# 4-20mA_Converter.net
KiCad netlist of a schematic drawn in Altium Designer
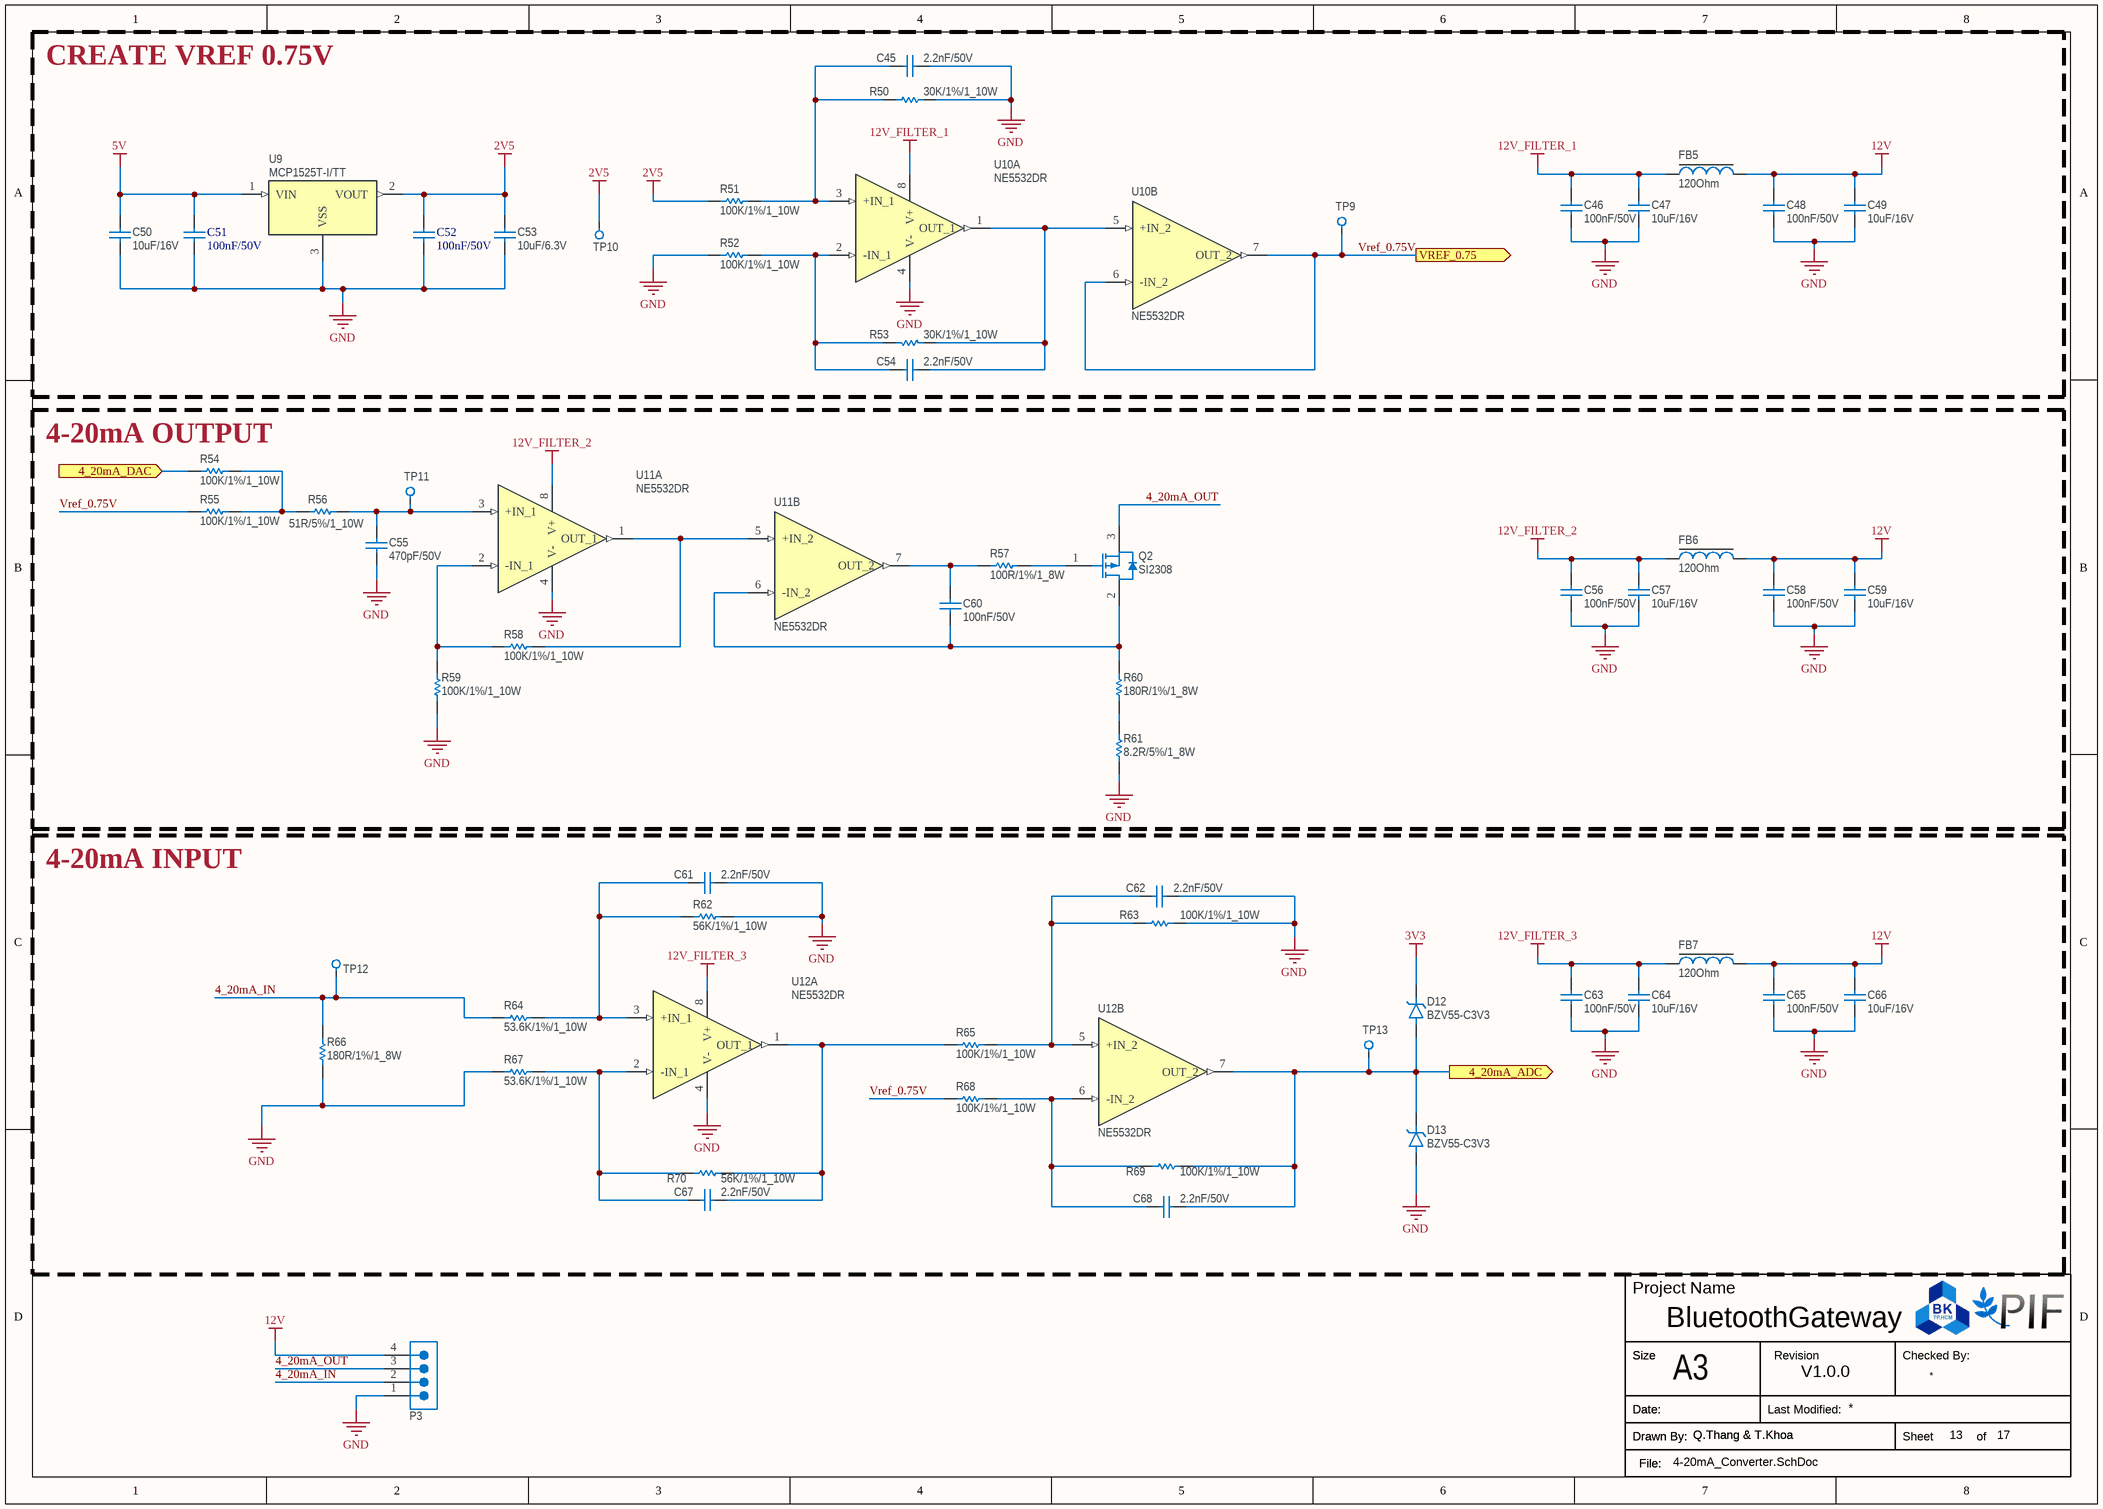
[diagram p0: 4-20mA_Converter.SchDoc]

(export (version "E")
  (design (tool "Eeschema 10.0.6"))
  (components
    (comp (ref "C45")
      (value "2.2nF/50V")
      (footprint "CAP_0603")
      (description "CAP, size 0603, 2.2nF, 50V")
      (fields (field (name "SUPPLY PART NUMBER") "CC0603KRX7R9BB222"))
      (libsource (lib "BluetoothTracking") (part "Ceramic_Cap_2.2nF_50V_0603"))
    )
    (comp (ref "C46")
      (value "100nF/50V")
      (footprint "CAP_0603")
      (description "CAP, size 0603, 100nF, 50V")
      (fields (field (name "SUPPLY PART NUMBER") "Tụ Gốm 0603 100nF (0.1uF) 50V"))
      (libsource (lib "BluetoothTracking") (part "Ceramic_Cap_100nF_50V_0603"))
    )
    (comp (ref "C47")
      (value "10uF/16V")
      (footprint "CAP_0603")
      (description "CAP, size 0603, 10uF, 16V")
      (fields (field (name "SUPPLY PART NUMBER") "Tụ Gốm 0603 10uF 16V"))
      (libsource (lib "BluetoothTracking") (part "Ceramic_Cap_10uF_16V_0603"))
    )
    (comp (ref "C48")
      (value "100nF/50V")
      (footprint "CAP_0603")
      (description "CAP, size 0603, 100nF, 50V")
      (fields (field (name "SUPPLY PART NUMBER") "Tụ Gốm 0603 100nF (0.1uF) 50V"))
      (libsource (lib "BluetoothTracking") (part "Ceramic_Cap_100nF_50V_0603"))
    )
    (comp (ref "C49")
      (value "10uF/16V")
      (footprint "CAP_0603")
      (description "CAP, size 0603, 10uF, 16V")
      (fields (field (name "SUPPLY PART NUMBER") "Tụ Gốm 0603 10uF 16V"))
      (libsource (lib "BluetoothTracking") (part "Ceramic_Cap_10uF_16V_0603"))
    )
    (comp (ref "C50")
      (value "10uF/16V")
      (footprint "CAP_0603")
      (description "CAP, size 0603, 10uF, 16V")
      (fields (field (name "SUPPLY PART NUMBER") "Tụ Gốm 0603 10uF 16V"))
      (libsource (lib "BluetoothTracking") (part "Ceramic_Cap_10uF_16V_0603"))
    )
    (comp (ref "C51")
      (value "100nF/50V")
      (footprint "CAP_0603")
      (description "CAP, size 0603, 100nF, 50V")
      (fields (field (name "SUPPLY PART NUMBER") "Tụ Gốm 0603 100nF (0.1uF) 50V"))
      (libsource (lib "BluetoothTracking") (part "Ceramic_Cap_100nF_50V_0603"))
    )
    (comp (ref "C52")
      (value "100nF/50V")
      (footprint "CAP_0603")
      (description "CAP, size 0603, 100nF, 50V")
      (fields (field (name "SUPPLY PART NUMBER") "Tụ Gốm 0603 100nF (0.1uF) 50V"))
      (libsource (lib "BluetoothTracking") (part "Ceramic_Cap_100nF_50V_0603"))
    )
    (comp (ref "C53")
      (value "10uF/6.3V")
      (footprint "CAP_0603")
      (description "CAP, size 0603, 10uF, 6.3V")
      (fields (field (name "SUPPLY PART NUMBER") "CC0603KRX5R5BB106"))
      (libsource (lib "BluetoothTracking") (part "Ceramic_Cap_10uF_6.3V_0603"))
    )
    (comp (ref "C54")
      (value "2.2nF/50V")
      (footprint "CAP_0603")
      (description "CAP, size 0603, 2.2nF, 50V")
      (fields (field (name "SUPPLY PART NUMBER") "CC0603KRX7R9BB222"))
      (libsource (lib "BluetoothTracking") (part "Ceramic_Cap_2.2nF_50V_0603"))
    )
    (comp (ref "C55")
      (value "470pF/50V")
      (footprint "CAP_0603")
      (description "CAP, size 0603, 470pF, 50V")
      (fields (field (name "SUPPLY PART NUMBER") "Tụ Gốm 0603 470pF 50V"))
      (libsource (lib "BluetoothTracking") (part "Ceramic_Cap_470pF_50V_0603"))
    )
    (comp (ref "C56")
      (value "100nF/50V")
      (footprint "CAP_0603")
      (description "CAP, size 0603, 100nF, 50V")
      (fields (field (name "SUPPLY PART NUMBER") "Tụ Gốm 0603 100nF (0.1uF) 50V"))
      (libsource (lib "BluetoothTracking") (part "Ceramic_Cap_100nF_50V_0603"))
    )
    (comp (ref "C57")
      (value "10uF/16V")
      (footprint "CAP_0603")
      (description "CAP, size 0603, 10uF, 16V")
      (fields (field (name "SUPPLY PART NUMBER") "Tụ Gốm 0603 10uF 16V"))
      (libsource (lib "BluetoothTracking") (part "Ceramic_Cap_10uF_16V_0603"))
    )
    (comp (ref "C58")
      (value "100nF/50V")
      (footprint "CAP_0603")
      (description "CAP, size 0603, 100nF, 50V")
      (fields (field (name "SUPPLY PART NUMBER") "Tụ Gốm 0603 100nF (0.1uF) 50V"))
      (libsource (lib "BluetoothTracking") (part "Ceramic_Cap_100nF_50V_0603"))
    )
    (comp (ref "C59")
      (value "10uF/16V")
      (footprint "CAP_0603")
      (description "CAP, size 0603, 10uF, 16V")
      (fields (field (name "SUPPLY PART NUMBER") "Tụ Gốm 0603 10uF 16V"))
      (libsource (lib "BluetoothTracking") (part "Ceramic_Cap_10uF_16V_0603"))
    )
    (comp (ref "C60")
      (value "100nF/50V")
      (footprint "CAP_0603")
      (description "CAP, size 0603, 100nF, 50V")
      (fields (field (name "SUPPLY PART NUMBER") "Tụ Gốm 0603 100nF (0.1uF) 50V"))
      (libsource (lib "BluetoothTracking") (part "Ceramic_Cap_100nF_50V_0603"))
    )
    (comp (ref "C61")
      (value "2.2nF/50V")
      (footprint "CAP_0603")
      (description "CAP, size 0603, 2.2nF, 50V")
      (fields (field (name "SUPPLY PART NUMBER") "CC0603KRX7R9BB222"))
      (libsource (lib "BluetoothTracking") (part "Ceramic_Cap_2.2nF_50V_0603"))
    )
    (comp (ref "C62")
      (value "2.2nF/50V")
      (footprint "CAP_0603")
      (description "CAP, size 0603, 2.2nF, 50V")
      (fields (field (name "SUPPLY PART NUMBER") "CC0603KRX7R9BB222"))
      (libsource (lib "BluetoothTracking") (part "Ceramic_Cap_2.2nF_50V_0603"))
    )
    (comp (ref "C63")
      (value "100nF/50V")
      (footprint "CAP_0603")
      (description "CAP, size 0603, 100nF, 50V")
      (fields (field (name "SUPPLY PART NUMBER") "Tụ Gốm 0603 100nF (0.1uF) 50V"))
      (libsource (lib "BluetoothTracking") (part "Ceramic_Cap_100nF_50V_0603"))
    )
    (comp (ref "C64")
      (value "10uF/16V")
      (footprint "CAP_0603")
      (description "CAP, size 0603, 10uF, 16V")
      (fields (field (name "SUPPLY PART NUMBER") "Tụ Gốm 0603 10uF 16V"))
      (libsource (lib "BluetoothTracking") (part "Ceramic_Cap_10uF_16V_0603"))
    )
    (comp (ref "C65")
      (value "100nF/50V")
      (footprint "CAP_0603")
      (description "CAP, size 0603, 100nF, 50V")
      (fields (field (name "SUPPLY PART NUMBER") "Tụ Gốm 0603 100nF (0.1uF) 50V"))
      (libsource (lib "BluetoothTracking") (part "Ceramic_Cap_100nF_50V_0603"))
    )
    (comp (ref "C66")
      (value "10uF/16V")
      (footprint "CAP_0603")
      (description "CAP, size 0603, 10uF, 16V")
      (fields (field (name "SUPPLY PART NUMBER") "Tụ Gốm 0603 10uF 16V"))
      (libsource (lib "BluetoothTracking") (part "Ceramic_Cap_10uF_16V_0603"))
    )
    (comp (ref "C67")
      (value "2.2nF/50V")
      (footprint "CAP_0603")
      (description "CAP, size 0603, 2.2nF, 50V")
      (fields (field (name "SUPPLY PART NUMBER") "CC0603KRX7R9BB222"))
      (libsource (lib "BluetoothTracking") (part "Ceramic_Cap_2.2nF_50V_0603"))
    )
    (comp (ref "C68")
      (value "2.2nF/50V")
      (footprint "CAP_0603")
      (description "CAP, size 0603, 2.2nF, 50V")
      (fields (field (name "SUPPLY PART NUMBER") "CC0603KRX7R9BB222"))
      (libsource (lib "BluetoothTracking") (part "Ceramic_Cap_2.2nF_50V_0603"))
    )
    (comp (ref "D12")
      (value "BZV55-C3V3")
      (footprint "SOD-80")
      (description "DIODE ZENER 3.3V 500 mW")
      (libsource (lib "BluetoothTracking") (part "Diode_BZV55C3V3"))
    )
    (comp (ref "D13")
      (value "BZV55-C3V3")
      (footprint "SOD-80")
      (description "DIODE ZENER 3.3V 500 mW")
      (libsource (lib "BluetoothTracking") (part "Diode_BZV55C3V3"))
    )
    (comp (ref "FB5")
      (value "120Ohm")
      (footprint "Ferrite_Bead_0805")
      (description "Ferrite Bead, size 0805, 120Ohm, 2A")
      (fields (field (name "SUPPLY PART NUMBER") "CBW201209U121T Ferrite Beads 2A 120 Ohm 0805"))
      (libsource (lib "BluetoothTracking") (part "Ferrite_Bead_120Ohm_2A_0805"))
    )
    (comp (ref "FB6")
      (value "120Ohm")
      (footprint "Ferrite_Bead_0805")
      (description "Ferrite Bead, size 0805, 120Ohm, 2A")
      (fields (field (name "SUPPLY PART NUMBER") "CBW201209U121T Ferrite Beads 2A 120 Ohm 0805"))
      (libsource (lib "BluetoothTracking") (part "Ferrite_Bead_120Ohm_2A_0805"))
    )
    (comp (ref "FB7")
      (value "120Ohm")
      (footprint "Ferrite_Bead_0805")
      (description "Ferrite Bead, size 0805, 120Ohm, 2A")
      (fields (field (name "SUPPLY PART NUMBER") "CBW201209U121T Ferrite Beads 2A 120 Ohm 0805"))
      (libsource (lib "BluetoothTracking") (part "Ferrite_Bead_120Ohm_2A_0805"))
    )
    (comp (ref "P3")
      (value "3.81mm_4P")
      (footprint "Terminal_Block_3.81mm_4P")
      (description "Terminal Block THT, pitch 3.81mm, 4p, 300V 10A")
      (fields
        (field (name "SUPPLY PART NUMBER") "UL-3.81-4-R Terminal Block Plug-in Hàn PCB 4 Chân Cong 3.81mm 300V 10A ULO")
      )
      (libsource (lib "BluetoothTracking") (part "Terminal_Block_3.81mm_4P"))
    )
    (comp (ref "Q2")
      (value "SI2308")
      (footprint "SOT-23")
      (description "SI2308 SOT23 MOSFET N-CH 2A 60V")
      (libsource (lib "BluetoothTracking") (part "SI2308"))
    )
    (comp (ref "R50")
      (value "30K/1%/1_10W")
      (footprint "Resistor_0603")
      (description "Resistor 0603 30KOhm 1% 1_10W")
      (fields (field (name "SUPPLY PART NUMBER") "Điện Trở 30 KOhm 0603 1%"))
      (libsource (lib "BluetoothTracking") (part "Res_30K_0603_1%"))
    )
    (comp (ref "R51")
      (value "100K/1%/1_10W")
      (footprint "Resistor_0603")
      (description "Resistor 0603 100KOhm 1% 1_10W")
      (fields (field (name "SUPPLY PART NUMBER") "Điện Trở 100 KOhm 0603 1%"))
      (libsource (lib "BluetoothTracking") (part "Res_100K_0603_1%"))
    )
    (comp (ref "R52")
      (value "100K/1%/1_10W")
      (footprint "Resistor_0603")
      (description "Resistor 0603 100KOhm 1% 1_10W")
      (fields (field (name "SUPPLY PART NUMBER") "Điện Trở 100 KOhm 0603 1%"))
      (libsource (lib "BluetoothTracking") (part "Res_100K_0603_1%"))
    )
    (comp (ref "R53")
      (value "30K/1%/1_10W")
      (footprint "Resistor_0603")
      (description "Resistor 0603 30KOhm 1% 1_10W")
      (fields (field (name "SUPPLY PART NUMBER") "Điện Trở 30 KOhm 0603 1%"))
      (libsource (lib "BluetoothTracking") (part "Res_30K_0603_1%"))
    )
    (comp (ref "R54")
      (value "100K/1%/1_10W")
      (footprint "Resistor_0603")
      (description "Resistor 0603 100KOhm 1% 1_10W")
      (fields (field (name "SUPPLY PART NUMBER") "Điện Trở 100 KOhm 0603 1%"))
      (libsource (lib "BluetoothTracking") (part "Res_100K_0603_1%"))
    )
    (comp (ref "R55")
      (value "100K/1%/1_10W")
      (footprint "Resistor_0603")
      (description "Resistor 0603 100KOhm 1% 1_10W")
      (fields (field (name "SUPPLY PART NUMBER") "Điện Trở 100 KOhm 0603 1%"))
      (libsource (lib "BluetoothTracking") (part "Res_100K_0603_1%"))
    )
    (comp (ref "R56")
      (value "51R/5%/1_10W")
      (footprint "Resistor_0603")
      (description "Resistor 0603 51 Ohm 5% 1_10W")
      (fields (field (name "SUPPLY PART NUMBER") "Điện Trở 51 Ohm 0603 5%"))
      (libsource (lib "BluetoothTracking") (part "Res_51R_0603_5%"))
    )
    (comp (ref "R57")
      (value "100R/1%/1_8W")
      (footprint "Resistor_0603")
      (description "Resistor 0805 100 Ohm 1% 1_8W")
      (fields (field (name "SUPPLY PART NUMBER") "Điện Trở 100 Ohm 0805 1%"))
      (libsource (lib "BluetoothTracking") (part "Res_100R_0805_1%"))
    )
    (comp (ref "R58")
      (value "100K/1%/1_10W")
      (footprint "Resistor_0603")
      (description "Resistor 0603 100KOhm 1% 1_10W")
      (fields (field (name "SUPPLY PART NUMBER") "Điện Trở 100 KOhm 0603 1%"))
      (libsource (lib "BluetoothTracking") (part "Res_100K_0603_1%"))
    )
    (comp (ref "R59")
      (value "100K/1%/1_10W")
      (footprint "Resistor_0603")
      (description "Resistor 0603 100KOhm 1% 1_10W")
      (fields (field (name "SUPPLY PART NUMBER") "Điện Trở 100 KOhm 0603 1%"))
      (libsource (lib "BluetoothTracking") (part "Res_100K_0603_1%"))
    )
    (comp (ref "R60")
      (value "180R/1%/1_8W")
      (footprint "Resistor_0805")
      (description "Resistor 0805 180 Ohm 1% 1_8W")
      (fields (field (name "SUPPLY PART NUMBER") "Điện Trở 180 Ohm 0805 1%"))
      (libsource (lib "BluetoothTracking") (part "Res_180R_0805_1%"))
    )
    (comp (ref "R61")
      (value "8.2R/5%/1_8W")
      (footprint "Resistor_0805")
      (description "Resistor 0805 8.2 Ohm 5% 1_8W")
      (fields (field (name "SUPPLY PART NUMBER") "Điện Trở 8.2 Ohm 0805 5%"))
      (libsource (lib "BluetoothTracking") (part "Res_8.2R_0805_5%"))
    )
    (comp (ref "R62")
      (value "56K/1%/1_10W")
      (footprint "Resistor_0603")
      (description "Resistor 0603 56KOhm 1% 1_10W")
      (fields (field (name "SUPPLY PART NUMBER") "Điện Trở 56 KOhm 0603 1%"))
      (libsource (lib "BluetoothTracking") (part "Res_56K_0603_1%"))
    )
    (comp (ref "R63")
      (value "100K/1%/1_10W")
      (footprint "Resistor_0603")
      (description "Resistor 0603 100KOhm 1% 1_10W")
      (fields (field (name "SUPPLY PART NUMBER") "Điện Trở 100 KOhm 0603 1%"))
      (libsource (lib "BluetoothTracking") (part "Res_100K_0603_1%"))
    )
    (comp (ref "R64")
      (value "53.6K/1%/1_10W")
      (footprint "Resistor_0603")
      (description "Resistor 0603 53.6KOhm 1% 1_10W")
      (fields (field (name "SUPPLY PART NUMBER") "Điện Trở 53.6 KOhm 0603 1%"))
      (libsource (lib "BluetoothTracking") (part "Res_53.6K_0603_1%"))
    )
    (comp (ref "R65")
      (value "100K/1%/1_10W")
      (footprint "Resistor_0603")
      (description "Resistor 0603 100KOhm 1% 1_10W")
      (fields (field (name "SUPPLY PART NUMBER") "Điện Trở 100 KOhm 0603 1%"))
      (libsource (lib "BluetoothTracking") (part "Res_100K_0603_1%"))
    )
    (comp (ref "R66")
      (value "180R/1%/1_8W")
      (footprint "Resistor_0805")
      (description "Resistor 0805 180 Ohm 1% 1_8W")
      (fields (field (name "SUPPLY PART NUMBER") "Điện Trở 180 Ohm 0805 1%"))
      (libsource (lib "BluetoothTracking") (part "Res_180R_0805_1%"))
    )
    (comp (ref "R67")
      (value "53.6K/1%/1_10W")
      (footprint "Resistor_0603")
      (description "Resistor 0603 53.6KOhm 1% 1_10W")
      (fields (field (name "SUPPLY PART NUMBER") "Điện Trở 53.6 KOhm 0603 1%"))
      (libsource (lib "BluetoothTracking") (part "Res_53.6K_0603_1%"))
    )
    (comp (ref "R68")
      (value "100K/1%/1_10W")
      (footprint "Resistor_0603")
      (description "Resistor 0603 100KOhm 1% 1_10W")
      (fields (field (name "SUPPLY PART NUMBER") "Điện Trở 100 KOhm 0603 1%"))
      (libsource (lib "BluetoothTracking") (part "Res_100K_0603_1%"))
    )
    (comp (ref "R69")
      (value "100K/1%/1_10W")
      (footprint "Resistor_0603")
      (description "Resistor 0603 100KOhm 1% 1_10W")
      (fields (field (name "SUPPLY PART NUMBER") "Điện Trở 100 KOhm 0603 1%"))
      (libsource (lib "BluetoothTracking") (part "Res_100K_0603_1%"))
    )
    (comp (ref "R70")
      (value "56K/1%/1_10W")
      (footprint "Resistor_0603")
      (description "Resistor 0603 56KOhm 1% 1_10W")
      (fields (field (name "SUPPLY PART NUMBER") "Điện Trở 56 KOhm 0603 1%"))
      (libsource (lib "BluetoothTracking") (part "Res_56K_0603_1%"))
    )
    (comp (ref "TP9")
      (value "VREF_0.75V")
      (footprint "TestPoint_Pad_3.0x3.0mm")
      (libsource (lib "BluetoothTracking") (part "Testpoint_SMD"))
    )
    (comp (ref "TP10")
      (value "2V5")
      (footprint "TestPoint_Pad_3.0x3.0mm")
      (libsource (lib "BluetoothTracking") (part "Testpoint_SMD"))
    )
    (comp (ref "TP11")
      (value "4-20mA_DAC")
      (footprint "TestPoint_THTPad_D1.5mm_Drill0.7mm")
      (description "Test Point TEST-1BK")
      (libsource (lib "BluetoothTracking") (part "Testpoint_TH"))
    )
    (comp (ref "TP12")
      (value "4_20mA_IN")
      (footprint "TestPoint_THTPad_D1.5mm_Drill0.7mm")
      (description "Test Point TEST-1BK")
      (libsource (lib "BluetoothTracking") (part "Testpoint_TH"))
    )
    (comp (ref "TP13")
      (value "4-20mA_ADC")
      (footprint "TestPoint_THTPad_D1.5mm_Drill0.7mm")
      (description "Test Point TEST-1BK")
      (libsource (lib "BluetoothTracking") (part "Testpoint_TH"))
    )
    (comp (ref "U9")
      (value "MCP1525T-I/TT")
      (footprint "SOT-23")
      (description "Voltage Reference IC 2.5V")
      (fields (field (name "SUPPLY PART NUMBER") "MCP1525T-I/TT IC Tham Chiếu Điện Áp 2.5V SOT-23"))
      (libsource (lib "BluetoothTracking") (part "MCP1525T-I/TT"))
    )
    (comp (ref "U10")
      (value "NE5532DR")
      (footprint "SOIC-8")
      (description "Low Noise Single/Dual Operational Amplifier - SOIC-8")
      (libsource (lib "BluetoothTracking") (part "NE5532DR"))
    )
    (comp (ref "U11")
      (value "NE5532DR")
      (footprint "SOIC-8")
      (description "Low Noise Single/Dual Operational Amplifier - SOIC-8")
      (libsource (lib "BluetoothTracking") (part "NE5532DR"))
    )
    (comp (ref "U12")
      (value "NE5532DR")
      (footprint "SOIC-8")
      (description "Low Noise Single/Dual Operational Amplifier - SOIC-8")
      (libsource (lib "BluetoothTracking") (part "NE5532DR"))
    )
  )
  (nets
    (net (code "1") (name "/4_20mA_ADC") (class "Default")
      (node (ref "C68") (pin "2") (pinfunction "2_2") (pintype "passive"))
      (node (ref "D12") (pin "A") (pinfunction "A_A") (pintype "passive"))
      (node (ref "D13") (pin "C") (pinfunction "C_C") (pintype "passive"))
      (node (ref "R69") (pin "2") (pinfunction "2_2") (pintype "passive"))
      (node (ref "TP13") (pin "1") (pinfunction "1_1") (pintype "passive"))
      (node (ref "U12") (pin "7") (pinfunction "OUT_2_7") (pintype "output"))
    )
    (net (code "2") (name "/4_20mA_DAC") (class "Default")
      (node (ref "R54") (pin "1") (pinfunction "1_1") (pintype "passive"))
    )
    (net (code "3") (name "/4_20mA_IN") (class "Default")
      (node (ref "P3") (pin "2") (pinfunction "2_2") (pintype "passive"))
      (node (ref "R64") (pin "1") (pinfunction "1_1") (pintype "passive"))
      (node (ref "R66") (pin "2") (pinfunction "2_2") (pintype "passive"))
      (node (ref "TP12") (pin "1") (pinfunction "1_1") (pintype "passive"))
    )
    (net (code "4") (name "/4_20mA_OUT") (class "Default")
      (node (ref "P3") (pin "3") (pinfunction "3_3") (pintype "passive"))
      (node (ref "Q2") (pin "3") (pinfunction "DRAIN_3") (pintype "passive"))
    )
    (net (code "5") (name "/Vref_0.75V") (class "Default")
      (node (ref "R55") (pin "1") (pinfunction "1_1") (pintype "passive"))
      (node (ref "R68") (pin "1") (pinfunction "1_1") (pintype "passive"))
      (node (ref "TP9") (pin "1") (pinfunction "1_1") (pintype "passive"))
      (node (ref "U10") (pin "6") (pinfunction "-IN_2_6") (pintype "input"))
      (node (ref "U10") (pin "7") (pinfunction "OUT_2_7") (pintype "output"))
    )
    (net (code "6") (name "2V5") (class "Default")
      (node (ref "C52") (pin "2") (pinfunction "2_2") (pintype "passive"))
      (node (ref "C53") (pin "2") (pinfunction "2_2") (pintype "passive"))
      (node (ref "R51") (pin "1") (pinfunction "1_1") (pintype "passive"))
      (node (ref "TP10") (pin "1") (pinfunction "1_1") (pintype "passive"))
      (node (ref "U9") (pin "2") (pinfunction "VOUT_2") (pintype "output"))
    )
    (net (code "7") (name "3V3") (class "Default")
      (node (ref "D12") (pin "C") (pinfunction "C_C") (pintype "passive"))
    )
    (net (code "8") (name "5V") (class "Default")
      (node (ref "C50") (pin "2") (pinfunction "2_2") (pintype "passive"))
      (node (ref "C51") (pin "2") (pinfunction "2_2") (pintype "passive"))
      (node (ref "U9") (pin "1") (pinfunction "VIN_1") (pintype "input"))
    )
    (net (code "9") (name "12V") (class "Default")
      (node (ref "C48") (pin "2") (pinfunction "2_2") (pintype "passive"))
      (node (ref "C49") (pin "2") (pinfunction "2_2") (pintype "passive"))
      (node (ref "C58") (pin "2") (pinfunction "2_2") (pintype "passive"))
      (node (ref "C59") (pin "2") (pinfunction "2_2") (pintype "passive"))
      (node (ref "C65") (pin "2") (pinfunction "2_2") (pintype "passive"))
      (node (ref "C66") (pin "2") (pinfunction "2_2") (pintype "passive"))
      (node (ref "FB5") (pin "2") (pinfunction "2_2") (pintype "passive"))
      (node (ref "FB6") (pin "2") (pinfunction "2_2") (pintype "passive"))
      (node (ref "FB7") (pin "2") (pinfunction "2_2") (pintype "passive"))
      (node (ref "P3") (pin "4") (pinfunction "4_4") (pintype "passive"))
    )
    (net (code "10") (name "12V_FILTER_1") (class "Default")
      (node (ref "C46") (pin "2") (pinfunction "2_2") (pintype "passive"))
      (node (ref "C47") (pin "2") (pinfunction "2_2") (pintype "passive"))
      (node (ref "FB5") (pin "1") (pinfunction "1_1") (pintype "passive"))
      (node (ref "U10") (pin "8") (pinfunction "V+_8") (pintype "power_in"))
    )
    (net (code "11") (name "12V_FILTER_2") (class "Default")
      (node (ref "C56") (pin "2") (pinfunction "2_2") (pintype "passive"))
      (node (ref "C57") (pin "2") (pinfunction "2_2") (pintype "passive"))
      (node (ref "FB6") (pin "1") (pinfunction "1_1") (pintype "passive"))
      (node (ref "U11") (pin "8") (pinfunction "V+_8") (pintype "power_in"))
    )
    (net (code "12") (name "12V_FILTER_3") (class "Default")
      (node (ref "C63") (pin "2") (pinfunction "2_2") (pintype "passive"))
      (node (ref "C64") (pin "2") (pinfunction "2_2") (pintype "passive"))
      (node (ref "FB7") (pin "1") (pinfunction "1_1") (pintype "passive"))
      (node (ref "U12") (pin "8") (pinfunction "V+_8") (pintype "power_in"))
    )
    (net (code "13") (name "GND") (class "Default")
      (node (ref "C45") (pin "2") (pinfunction "2_2") (pintype "passive"))
      (node (ref "C46") (pin "1") (pinfunction "1_1") (pintype "passive"))
      (node (ref "C47") (pin "1") (pinfunction "1_1") (pintype "passive"))
      (node (ref "C48") (pin "1") (pinfunction "1_1") (pintype "passive"))
      (node (ref "C49") (pin "1") (pinfunction "1_1") (pintype "passive"))
      (node (ref "C50") (pin "1") (pinfunction "1_1") (pintype "passive"))
      (node (ref "C51") (pin "1") (pinfunction "1_1") (pintype "passive"))
      (node (ref "C52") (pin "1") (pinfunction "1_1") (pintype "passive"))
      (node (ref "C53") (pin "1") (pinfunction "1_1") (pintype "passive"))
      (node (ref "C55") (pin "1") (pinfunction "1_1") (pintype "passive"))
      (node (ref "C56") (pin "1") (pinfunction "1_1") (pintype "passive"))
      (node (ref "C57") (pin "1") (pinfunction "1_1") (pintype "passive"))
      (node (ref "C58") (pin "1") (pinfunction "1_1") (pintype "passive"))
      (node (ref "C59") (pin "1") (pinfunction "1_1") (pintype "passive"))
      (node (ref "C61") (pin "2") (pinfunction "2_2") (pintype "passive"))
      (node (ref "C62") (pin "2") (pinfunction "2_2") (pintype "passive"))
      (node (ref "C63") (pin "1") (pinfunction "1_1") (pintype "passive"))
      (node (ref "C64") (pin "1") (pinfunction "1_1") (pintype "passive"))
      (node (ref "C65") (pin "1") (pinfunction "1_1") (pintype "passive"))
      (node (ref "C66") (pin "1") (pinfunction "1_1") (pintype "passive"))
      (node (ref "D13") (pin "A") (pinfunction "A_A") (pintype "passive"))
      (node (ref "P3") (pin "1") (pinfunction "1_1") (pintype "passive"))
      (node (ref "R50") (pin "2") (pinfunction "2_2") (pintype "passive"))
      (node (ref "R52") (pin "1") (pinfunction "1_1") (pintype "passive"))
      (node (ref "R59") (pin "1") (pinfunction "1_1") (pintype "passive"))
      (node (ref "R61") (pin "2") (pinfunction "2_2") (pintype "passive"))
      (node (ref "R62") (pin "2") (pinfunction "2_2") (pintype "passive"))
      (node (ref "R63") (pin "2") (pinfunction "2_2") (pintype "passive"))
      (node (ref "R66") (pin "1") (pinfunction "1_1") (pintype "passive"))
      (node (ref "R67") (pin "1") (pinfunction "1_1") (pintype "passive"))
      (node (ref "U10") (pin "4") (pinfunction "V-_4") (pintype "power_in"))
      (node (ref "U11") (pin "4") (pinfunction "V-_4") (pintype "power_in"))
      (node (ref "U12") (pin "4") (pinfunction "V-_4") (pintype "power_in"))
      (node (ref "U9") (pin "3") (pinfunction "VSS_3") (pintype "passive"))
    )
    (net (code "14") (name "Net-(Q2-GATE)") (class "Default")
      (node (ref "Q2") (pin "1") (pinfunction "GATE_1") (pintype "passive"))
      (node (ref "R57") (pin "2") (pinfunction "2_2") (pintype "passive"))
    )
    (net (code "15") (name "Net-(Q2-SOURCE)") (class "Default")
      (node (ref "C60") (pin "1") (pinfunction "1_1") (pintype "passive"))
      (node (ref "Q2") (pin "2") (pinfunction "SOURCE_2") (pintype "passive"))
      (node (ref "R60") (pin "2") (pinfunction "2_2") (pintype "passive"))
      (node (ref "U11") (pin "6") (pinfunction "-IN_2_6") (pintype "input"))
    )
    (net (code "16") (name "Net-(R54-Pad2)") (class "Default")
      (node (ref "R54") (pin "2") (pinfunction "2_2") (pintype "passive"))
      (node (ref "R55") (pin "2") (pinfunction "2_2") (pintype "passive"))
      (node (ref "R56") (pin "1") (pinfunction "1_1") (pintype "passive"))
    )
    (net (code "17") (name "Net-(R60-Pad1)") (class "Default")
      (node (ref "R60") (pin "1") (pinfunction "1_1") (pintype "passive"))
      (node (ref "R61") (pin "1") (pinfunction "1_1") (pintype "passive"))
    )
    (net (code "18") (name "Net-(U10A-+IN_1)") (class "Default")
      (node (ref "C45") (pin "1") (pinfunction "1_1") (pintype "passive"))
      (node (ref "R50") (pin "1") (pinfunction "1_1") (pintype "passive"))
      (node (ref "R51") (pin "2") (pinfunction "2_2") (pintype "passive"))
      (node (ref "U10") (pin "3") (pinfunction "+IN_1_3") (pintype "input"))
    )
    (net (code "19") (name "Net-(U10A--IN_1)") (class "Default")
      (node (ref "C54") (pin "1") (pinfunction "1_1") (pintype "passive"))
      (node (ref "R52") (pin "2") (pinfunction "2_2") (pintype "passive"))
      (node (ref "R53") (pin "1") (pinfunction "1_1") (pintype "passive"))
      (node (ref "U10") (pin "2") (pinfunction "-IN_1_2") (pintype "input"))
    )
    (net (code "20") (name "Net-(U10A-OUT_1)") (class "Default")
      (node (ref "C54") (pin "2") (pinfunction "2_2") (pintype "passive"))
      (node (ref "R53") (pin "2") (pinfunction "2_2") (pintype "passive"))
      (node (ref "U10") (pin "1") (pinfunction "OUT_1_1") (pintype "output"))
      (node (ref "U10") (pin "5") (pinfunction "+IN_2_5") (pintype "input"))
    )
    (net (code "21") (name "Net-(U11A-+IN_1)") (class "Default")
      (node (ref "C55") (pin "2") (pinfunction "2_2") (pintype "passive"))
      (node (ref "R56") (pin "2") (pinfunction "2_2") (pintype "passive"))
      (node (ref "TP11") (pin "1") (pinfunction "1_1") (pintype "passive"))
      (node (ref "U11") (pin "3") (pinfunction "+IN_1_3") (pintype "input"))
    )
    (net (code "22") (name "Net-(U11A--IN_1)") (class "Default")
      (node (ref "R58") (pin "1") (pinfunction "1_1") (pintype "passive"))
      (node (ref "R59") (pin "2") (pinfunction "2_2") (pintype "passive"))
      (node (ref "U11") (pin "2") (pinfunction "-IN_1_2") (pintype "input"))
    )
    (net (code "23") (name "Net-(U11A-OUT_1)") (class "Default")
      (node (ref "R58") (pin "2") (pinfunction "2_2") (pintype "passive"))
      (node (ref "U11") (pin "1") (pinfunction "OUT_1_1") (pintype "output"))
      (node (ref "U11") (pin "5") (pinfunction "+IN_2_5") (pintype "input"))
    )
    (net (code "24") (name "Net-(U11B-OUT_2)") (class "Default")
      (node (ref "C60") (pin "2") (pinfunction "2_2") (pintype "passive"))
      (node (ref "R57") (pin "1") (pinfunction "1_1") (pintype "passive"))
      (node (ref "U11") (pin "7") (pinfunction "OUT_2_7") (pintype "output"))
    )
    (net (code "25") (name "Net-(U12A-+IN_1)") (class "Default")
      (node (ref "C61") (pin "1") (pinfunction "1_1") (pintype "passive"))
      (node (ref "R62") (pin "1") (pinfunction "1_1") (pintype "passive"))
      (node (ref "R64") (pin "2") (pinfunction "2_2") (pintype "passive"))
      (node (ref "U12") (pin "3") (pinfunction "+IN_1_3") (pintype "input"))
    )
    (net (code "26") (name "Net-(U12A--IN_1)") (class "Default")
      (node (ref "C67") (pin "1") (pinfunction "1_1") (pintype "passive"))
      (node (ref "R67") (pin "2") (pinfunction "2_2") (pintype "passive"))
      (node (ref "R70") (pin "1") (pinfunction "1_1") (pintype "passive"))
      (node (ref "U12") (pin "2") (pinfunction "-IN_1_2") (pintype "input"))
    )
    (net (code "27") (name "Net-(U12A-OUT_1)") (class "Default")
      (node (ref "C67") (pin "2") (pinfunction "2_2") (pintype "passive"))
      (node (ref "R65") (pin "1") (pinfunction "1_1") (pintype "passive"))
      (node (ref "R70") (pin "2") (pinfunction "2_2") (pintype "passive"))
      (node (ref "U12") (pin "1") (pinfunction "OUT_1_1") (pintype "output"))
    )
    (net (code "28") (name "Net-(U12B-+IN_2)") (class "Default")
      (node (ref "C62") (pin "1") (pinfunction "1_1") (pintype "passive"))
      (node (ref "R63") (pin "1") (pinfunction "1_1") (pintype "passive"))
      (node (ref "R65") (pin "2") (pinfunction "2_2") (pintype "passive"))
      (node (ref "U12") (pin "5") (pinfunction "+IN_2_5") (pintype "input"))
    )
    (net (code "29") (name "Net-(U12B--IN_2)") (class "Default")
      (node (ref "C68") (pin "1") (pinfunction "1_1") (pintype "passive"))
      (node (ref "R68") (pin "2") (pinfunction "2_2") (pintype "passive"))
      (node (ref "R69") (pin "1") (pinfunction "1_1") (pintype "passive"))
      (node (ref "U12") (pin "6") (pinfunction "-IN_2_6") (pintype "input"))
    )
  )
)
